# NCD_SHEET.net
KiCad netlist of a schematic drawn in Altium Designer
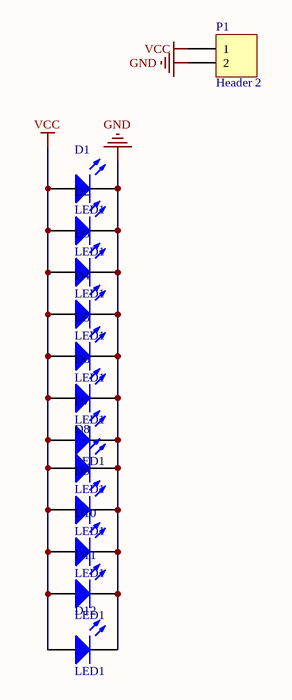
[diagram p0: NCD_SHEET.SchDoc]

(export (version "E")
  (design (tool "Eeschema 10.0.6"))
  (components
    (comp (ref "D1")
      (value "LED1")
      (footprint "KEMET Chip Capacitor:0603")
      (description "Typical RED GaAs LED")
      (fields (field (name "PUBLISHER") "Altium Limited"))
      (libsource (lib "Miscellaneous Devices") (part "LED1"))
    )
    (comp (ref "D2")
      (value "LED1")
      (footprint "KEMET Chip Capacitor:0603")
      (description "Typical RED GaAs LED")
      (fields (field (name "PUBLISHER") "Altium Limited"))
      (libsource (lib "Miscellaneous Devices") (part "LED1"))
    )
    (comp (ref "D3")
      (value "LED1")
      (footprint "KEMET Chip Capacitor:0603")
      (description "Typical RED GaAs LED")
      (fields (field (name "PUBLISHER") "Altium Limited"))
      (libsource (lib "Miscellaneous Devices") (part "LED1"))
    )
    (comp (ref "D4")
      (value "LED1")
      (footprint "KEMET Chip Capacitor:0603")
      (description "Typical RED GaAs LED")
      (fields (field (name "PUBLISHER") "Altium Limited"))
      (libsource (lib "Miscellaneous Devices") (part "LED1"))
    )
    (comp (ref "D5")
      (value "LED1")
      (footprint "KEMET Chip Capacitor:0603")
      (description "Typical RED GaAs LED")
      (fields (field (name "PUBLISHER") "Altium Limited"))
      (libsource (lib "Miscellaneous Devices") (part "LED1"))
    )
    (comp (ref "D6")
      (value "LED1")
      (footprint "KEMET Chip Capacitor:0603")
      (description "Typical RED GaAs LED")
      (fields (field (name "PUBLISHER") "Altium Limited"))
      (libsource (lib "Miscellaneous Devices") (part "LED1"))
    )
    (comp (ref "D7")
      (value "LED1")
      (footprint "KEMET Chip Capacitor:0603")
      (description "Typical RED GaAs LED")
      (fields (field (name "PUBLISHER") "Altium Limited"))
      (libsource (lib "Miscellaneous Devices") (part "LED1"))
    )
    (comp (ref "D8")
      (value "LED1")
      (footprint "KEMET Chip Capacitor:0603")
      (description "Typical RED GaAs LED")
      (fields (field (name "PUBLISHER") "Altium Limited"))
      (libsource (lib "Miscellaneous Devices") (part "LED1"))
    )
    (comp (ref "D9")
      (value "LED1")
      (footprint "KEMET Chip Capacitor:0603")
      (description "Typical RED GaAs LED")
      (fields (field (name "PUBLISHER") "Altium Limited"))
      (libsource (lib "Miscellaneous Devices") (part "LED1"))
    )
    (comp (ref "D10")
      (value "LED1")
      (footprint "KEMET Chip Capacitor:0603")
      (description "Typical RED GaAs LED")
      (fields (field (name "PUBLISHER") "Altium Limited"))
      (libsource (lib "Miscellaneous Devices") (part "LED1"))
    )
    (comp (ref "D11")
      (value "LED1")
      (footprint "KEMET Chip Capacitor:0603")
      (description "Typical RED GaAs LED")
      (fields (field (name "PUBLISHER") "Altium Limited"))
      (libsource (lib "Miscellaneous Devices") (part "LED1"))
    )
    (comp (ref "D12")
      (value "LED1")
      (footprint "KEMET Chip Capacitor:0603")
      (description "Typical RED GaAs LED")
      (fields (field (name "PUBLISHER") "Altium Limited"))
      (libsource (lib "Miscellaneous Devices") (part "LED1"))
    )
    (comp (ref "P1")
      (value "Header 2")
      (footprint "HDR1X2")
      (description "Header, 2-Pin")
      (fields (field (name "PUBLISHER") "Altium Limited"))
      (libsource (lib "Miscellaneous Connectors") (part "Header 2"))
    )
  )
  (nets
    (net (code "1") (name "GND") (class "Default")
      (node (ref "D1") (pin "2") (pinfunction "K_2") (pintype "passive"))
      (node (ref "D10") (pin "2") (pinfunction "K_2") (pintype "passive"))
      (node (ref "D11") (pin "2") (pinfunction "K_2") (pintype "passive"))
      (node (ref "D12") (pin "2") (pinfunction "K_2") (pintype "passive"))
      (node (ref "D2") (pin "2") (pinfunction "K_2") (pintype "passive"))
      (node (ref "D3") (pin "2") (pinfunction "K_2") (pintype "passive"))
      (node (ref "D4") (pin "2") (pinfunction "K_2") (pintype "passive"))
      (node (ref "D5") (pin "2") (pinfunction "K_2") (pintype "passive"))
      (node (ref "D6") (pin "2") (pinfunction "K_2") (pintype "passive"))
      (node (ref "D7") (pin "2") (pinfunction "K_2") (pintype "passive"))
      (node (ref "D8") (pin "2") (pinfunction "K_2") (pintype "passive"))
      (node (ref "D9") (pin "2") (pinfunction "K_2") (pintype "passive"))
      (node (ref "P1") (pin "2") (pinfunction "2_2") (pintype "passive"))
    )
    (net (code "2") (name "VCC") (class "Default")
      (node (ref "D1") (pin "1") (pinfunction "A_1") (pintype "passive"))
      (node (ref "D10") (pin "1") (pinfunction "A_1") (pintype "passive"))
      (node (ref "D11") (pin "1") (pinfunction "A_1") (pintype "passive"))
      (node (ref "D12") (pin "1") (pinfunction "A_1") (pintype "passive"))
      (node (ref "D2") (pin "1") (pinfunction "A_1") (pintype "passive"))
      (node (ref "D3") (pin "1") (pinfunction "A_1") (pintype "passive"))
      (node (ref "D4") (pin "1") (pinfunction "A_1") (pintype "passive"))
      (node (ref "D5") (pin "1") (pinfunction "A_1") (pintype "passive"))
      (node (ref "D6") (pin "1") (pinfunction "A_1") (pintype "passive"))
      (node (ref "D7") (pin "1") (pinfunction "A_1") (pintype "passive"))
      (node (ref "D8") (pin "1") (pinfunction "A_1") (pintype "passive"))
      (node (ref "D9") (pin "1") (pinfunction "A_1") (pintype "passive"))
      (node (ref "P1") (pin "1") (pinfunction "1_1") (pintype "passive"))
    )
  )
)
